# RS-485.net
KiCad netlist of a schematic drawn in Altium Designer
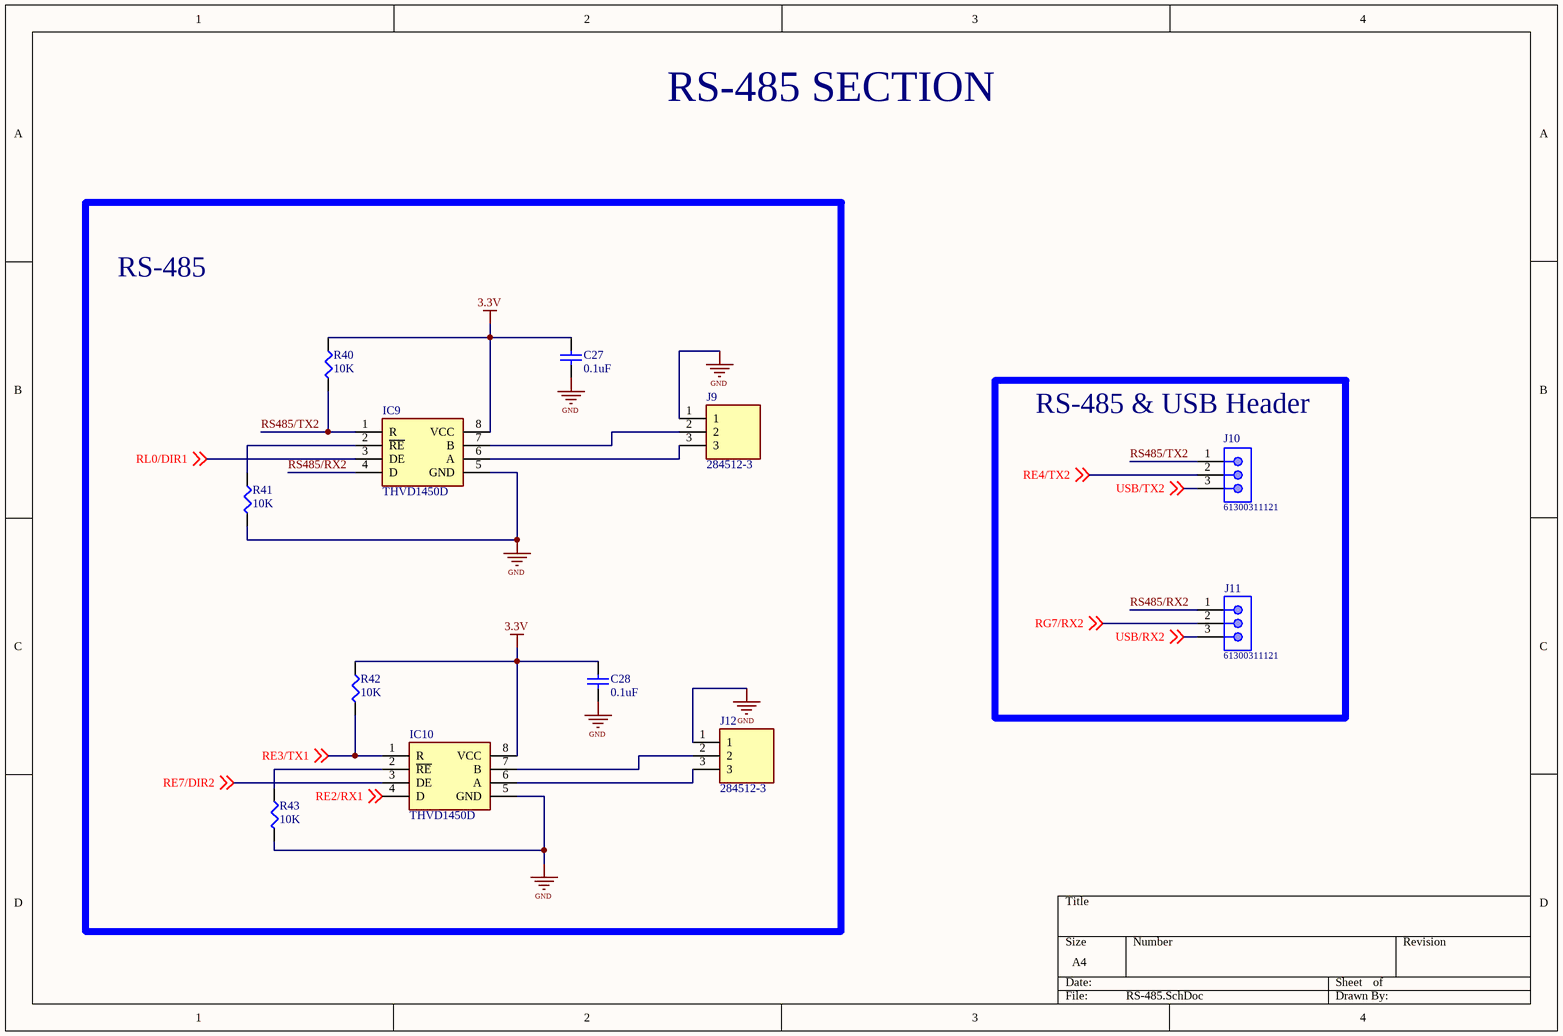
[diagram p0: RS-485.SchDoc]

(export (version "E")
  (design (tool "Eeschema 10.0.6"))
  (components
    (comp (ref "C27")
      (value "0.1uF")
      (footprint "C1206")
      (description "Capacitor (Semiconductor SIM Model)")
      (fields
        (field (name "PART NUMBER") "C0603C100M5HACTU")
        (field (name "Comment") "10pF")
        (field (name "PUBLISHER") "Altium Limited")
        (field (name "SOURCE") "Mouser")
      )
      (libsource (lib "Miscellaneous Devices") (part "Cap Semi"))
    )
    (comp (ref "C28")
      (value "0.1uF")
      (footprint "C1206")
      (description "Capacitor (Semiconductor SIM Model)")
      (fields
        (field (name "PART NUMBER") "C0603C100M5HACTU")
        (field (name "Comment") "10pF")
        (field (name "PUBLISHER") "Altium Limited")
        (field (name "SOURCE") "Mouser")
      )
      (libsource (lib "Miscellaneous Devices") (part "Cap Semi"))
    )
    (comp (ref "IC9")
      (value "THVD1450D")
      (footprint "SamacSys:SOIC127P600X175-8N")
      (description "Integrated Circuit")
      (fields (field (name "MOUSER PART NUMBER") "595-THVD1450D"))
      (libsource (lib "*") (part "THVD1450D"))
    )
    (comp (ref "IC10")
      (value "THVD1450D")
      (footprint "SamacSys:SOIC127P600X175-8N")
      (description "Integrated Circuit")
      (fields (field (name "MOUSER PART NUMBER") "595-THVD1450D"))
      (libsource (lib "*") (part "THVD1450D"))
    )
    (comp (ref "J9")
      (value "284512-3")
      (footprint "SamacSys:SHDRRA3W80P0X350_1X3_1250X920X745P")
      (description "Connector")
      (fields (field (name "MOUSER PART NUMBER") "571-284512-3"))
      (libsource (lib "*") (part "284512-3"))
    )
    (comp (ref "J10")
      (value "61300311121")
      (footprint "61300311121")
      (description "WR-PHD Pin Header, THT, pitch 2.54mm, Single Row, Vertical, 3pin")
      (fields (field (name "PUBLISHER") "Wurth Elektronik"))
      (libsource (lib "SIL_Connectors WR-PHD_rev19a") (part "61300311121"))
    )
    (comp (ref "J11")
      (value "61300311121")
      (footprint "61300311121")
      (description "WR-PHD Pin Header, THT, pitch 2.54mm, Single Row, Vertical, 3pin")
      (fields (field (name "PUBLISHER") "Wurth Elektronik"))
      (libsource (lib "SIL_Connectors WR-PHD_rev19a") (part "61300311121"))
    )
    (comp (ref "J12")
      (value "284512-3")
      (footprint "SamacSys:SHDRRA3W80P0X350_1X3_1250X920X745P")
      (description "Connector")
      (fields (field (name "MOUSER PART NUMBER") "571-284512-3"))
      (libsource (lib "*") (part "284512-3"))
    )
    (comp (ref "R40")
      (value "10K")
      (footprint "SMD-0805-RES")
      (description "RES SMD 1K OHM 1% 1/8W 0805")
      (fields
        (field (name "PART NUMBER") "ERJ-6ENF1001V")
        (field (name "DIGI-KEY PART NUMBER") "P1.00KCCT-ND")
      )
      (libsource (lib "Panasonic_ERJ_0805") (part "ERJ-6ENF1001V"))
    )
    (comp (ref "R41")
      (value "10K")
      (footprint "SMD-0805-RES")
      (description "RES SMD 1K OHM 1% 1/8W 0805")
      (fields
        (field (name "PART NUMBER") "ERJ-6ENF1001V")
        (field (name "DIGI-KEY PART NUMBER") "P1.00KCCT-ND")
      )
      (libsource (lib "Panasonic_ERJ_0805") (part "ERJ-6ENF1001V"))
    )
    (comp (ref "R42")
      (value "10K")
      (footprint "SMD-0805-RES")
      (description "RES SMD 1K OHM 1% 1/8W 0805")
      (fields
        (field (name "PART NUMBER") "ERJ-6ENF1001V")
        (field (name "DIGI-KEY PART NUMBER") "P1.00KCCT-ND")
      )
      (libsource (lib "Panasonic_ERJ_0805") (part "ERJ-6ENF1001V"))
    )
    (comp (ref "R43")
      (value "10K")
      (footprint "SMD-0805-RES")
      (description "RES SMD 1K OHM 1% 1/8W 0805")
      (fields
        (field (name "PART NUMBER") "ERJ-6ENF1001V")
        (field (name "DIGI-KEY PART NUMBER") "P1.00KCCT-ND")
      )
      (libsource (lib "Panasonic_ERJ_0805") (part "ERJ-6ENF1001V"))
    )
  )
  (nets
    (net (code "1") (name "/RS485{slash}RX2") (class "Default")
      (node (ref "IC9") (pin "4") (pinfunction "D_4") (pintype "passive"))
      (node (ref "J11") (pin "1") (pinfunction "1_1") (pintype "passive"))
    )
    (net (code "2") (name "/RS485{slash}TX2") (class "Default")
      (node (ref "IC9") (pin "1") (pinfunction "R_1") (pintype "passive"))
      (node (ref "J10") (pin "1") (pinfunction "1_1") (pintype "passive"))
      (node (ref "R40") (pin "2") (pinfunction "2_2") (pintype "passive"))
    )
    (net (code "3") (name "3.3V") (class "Default")
      (node (ref "C27") (pin "2") (pinfunction "2_2") (pintype "passive"))
      (node (ref "C28") (pin "2") (pinfunction "2_2") (pintype "passive"))
      (node (ref "IC10") (pin "8") (pinfunction "VCC_8") (pintype "passive"))
      (node (ref "IC9") (pin "8") (pinfunction "VCC_8") (pintype "passive"))
      (node (ref "R40") (pin "1") (pinfunction "1_1") (pintype "passive"))
      (node (ref "R42") (pin "1") (pinfunction "1_1") (pintype "passive"))
    )
    (net (code "4") (name "GND") (class "Default")
      (node (ref "C27") (pin "1") (pinfunction "1_1") (pintype "passive"))
      (node (ref "C28") (pin "1") (pinfunction "1_1") (pintype "passive"))
      (node (ref "IC10") (pin "5") (pinfunction "GND_5") (pintype "passive"))
      (node (ref "IC9") (pin "5") (pinfunction "GND_5") (pintype "passive"))
      (node (ref "J12") (pin "1") (pinfunction "1_1") (pintype "passive"))
      (node (ref "J9") (pin "1") (pinfunction "1_1") (pintype "passive"))
      (node (ref "R41") (pin "2") (pinfunction "2_2") (pintype "passive"))
      (node (ref "R43") (pin "2") (pinfunction "2_2") (pintype "passive"))
    )
    (net (code "5") (name "Net-(IC9-A)") (class "Default")
      (node (ref "IC9") (pin "6") (pinfunction "A_6") (pintype "passive"))
      (node (ref "J9") (pin "3") (pinfunction "3_3") (pintype "passive"))
    )
    (net (code "6") (name "Net-(IC9-B)") (class "Default")
      (node (ref "IC9") (pin "7") (pinfunction "B_7") (pintype "passive"))
      (node (ref "J9") (pin "2") (pinfunction "2_2") (pintype "passive"))
    )
    (net (code "7") (name "Net-(IC9-~{RE})") (class "Default")
      (node (ref "IC9") (pin "2") (pinfunction "~{RE}_2") (pintype "passive"))
      (node (ref "R41") (pin "1") (pinfunction "1_1") (pintype "passive"))
    )
    (net (code "8") (name "Net-(IC10-A)") (class "Default")
      (node (ref "IC10") (pin "6") (pinfunction "A_6") (pintype "passive"))
      (node (ref "J12") (pin "3") (pinfunction "3_3") (pintype "passive"))
    )
    (net (code "9") (name "Net-(IC10-B)") (class "Default")
      (node (ref "IC10") (pin "7") (pinfunction "B_7") (pintype "passive"))
      (node (ref "J12") (pin "2") (pinfunction "2_2") (pintype "passive"))
    )
    (net (code "10") (name "Net-(IC10-~{RE})") (class "Default")
      (node (ref "IC10") (pin "2") (pinfunction "~{RE}_2") (pintype "passive"))
      (node (ref "R43") (pin "1") (pinfunction "1_1") (pintype "passive"))
    )
    (net (code "11") (name "RE2{slash}RX1") (class "Default")
      (node (ref "IC10") (pin "4") (pinfunction "D_4") (pintype "passive"))
    )
    (net (code "12") (name "RE3{slash}TX1") (class "Default")
      (node (ref "IC10") (pin "1") (pinfunction "R_1") (pintype "passive"))
      (node (ref "R42") (pin "2") (pinfunction "2_2") (pintype "passive"))
    )
    (net (code "13") (name "RE4{slash}TX2") (class "Default")
      (node (ref "J10") (pin "2") (pinfunction "2_2") (pintype "passive"))
    )
    (net (code "14") (name "RE7{slash}DIR2") (class "Default")
      (node (ref "IC10") (pin "3") (pinfunction "DE_3") (pintype "passive"))
    )
    (net (code "15") (name "RG7{slash}RX2") (class "Default")
      (node (ref "J11") (pin "2") (pinfunction "2_2") (pintype "passive"))
    )
    (net (code "16") (name "RL0{slash}DIR1") (class "Default")
      (node (ref "IC9") (pin "3") (pinfunction "DE_3") (pintype "passive"))
    )
    (net (code "17") (name "USB{slash}RX2") (class "Default")
      (node (ref "J11") (pin "3") (pinfunction "3_3") (pintype "passive"))
    )
    (net (code "18") (name "USB{slash}TX2") (class "Default")
      (node (ref "J10") (pin "3") (pinfunction "3_3") (pintype "passive"))
    )
  )
)
